# B152X.net
KiCad netlist of a schematic drawn in EAGLE
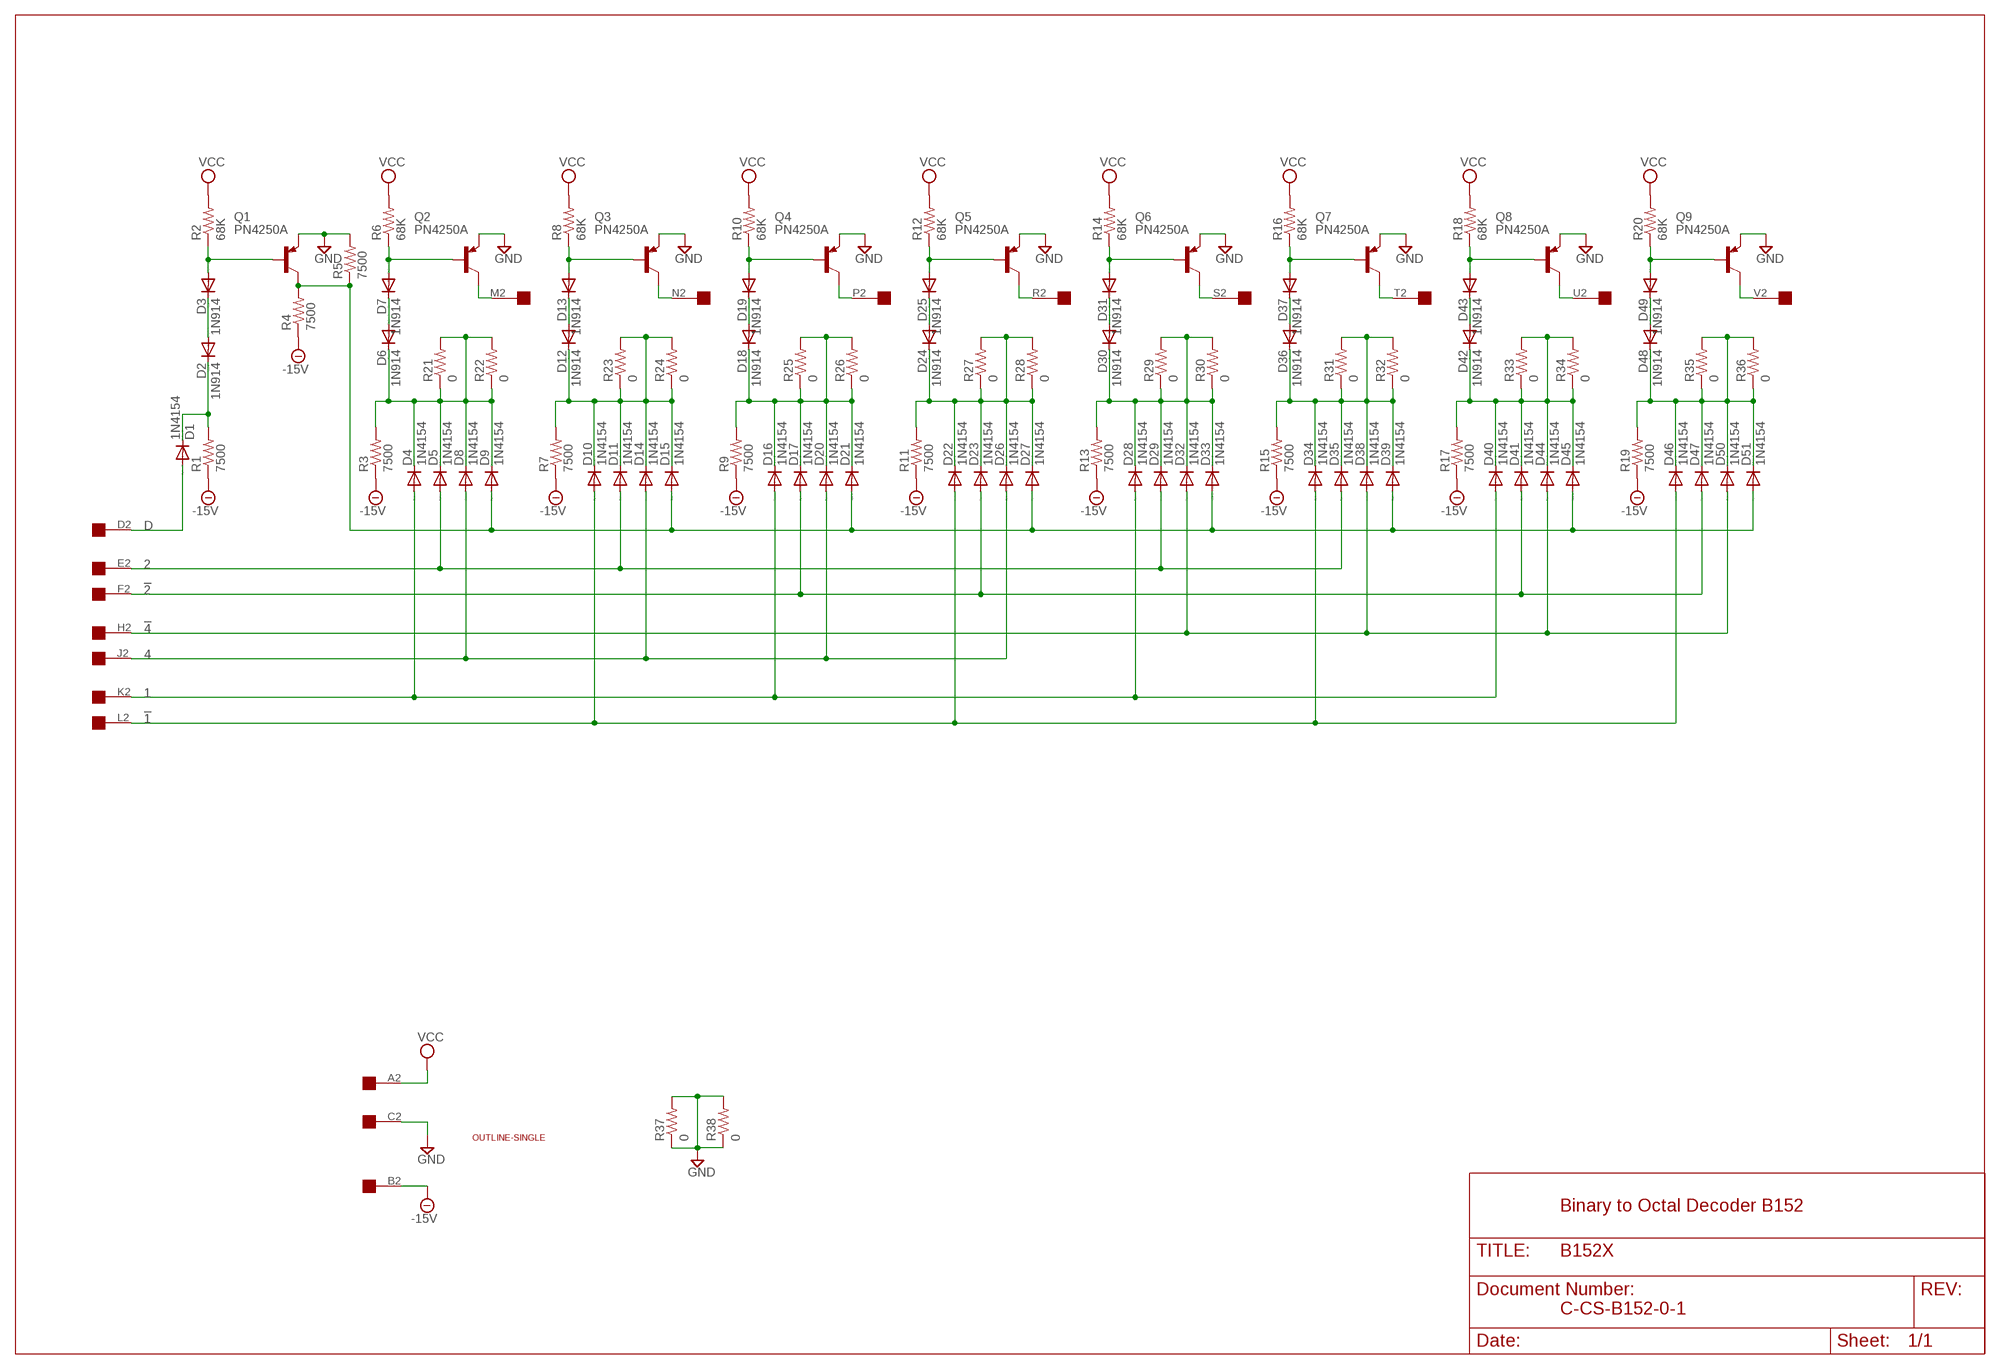
[diagram p0: schematic, sheet 1]

(export (version "E")
  (design (tool "Eeschema 10.0.6"))
  (components
    (comp (ref "D1")
      (value "1N4154")
      (footprint "eagle-import:DO35-10")
      (libsource (lib "eagle-import") (part "DIODE-DO35-10"))
    )
    (comp (ref "D2")
      (value "1N914")
      (footprint "eagle-import:DO35-10")
      (libsource (lib "eagle-import") (part "DIODE-DO35-10"))
    )
    (comp (ref "D3")
      (value "1N914")
      (footprint "eagle-import:DO35-10")
      (libsource (lib "eagle-import") (part "DIODE-DO35-10"))
    )
    (comp (ref "D4")
      (value "1N4154")
      (footprint "eagle-import:DO35-10")
      (libsource (lib "eagle-import") (part "DIODE-DO35-10"))
    )
    (comp (ref "D5")
      (value "1N4154")
      (footprint "eagle-import:DO35-10")
      (libsource (lib "eagle-import") (part "DIODE-DO35-10"))
    )
    (comp (ref "D6")
      (value "1N914")
      (footprint "eagle-import:DO35-10")
      (libsource (lib "eagle-import") (part "DIODE-DO35-10"))
    )
    (comp (ref "D7")
      (value "1N914")
      (footprint "eagle-import:DO35-10")
      (libsource (lib "eagle-import") (part "DIODE-DO35-10"))
    )
    (comp (ref "D8")
      (value "1N4154")
      (footprint "eagle-import:DO35-10")
      (libsource (lib "eagle-import") (part "DIODE-DO35-10"))
    )
    (comp (ref "D9")
      (value "1N4154")
      (footprint "eagle-import:DO35-10")
      (libsource (lib "eagle-import") (part "DIODE-DO35-10"))
    )
    (comp (ref "D10")
      (value "1N4154")
      (footprint "eagle-import:DO35-10")
      (libsource (lib "eagle-import") (part "DIODE-DO35-10"))
    )
    (comp (ref "D11")
      (value "1N4154")
      (footprint "eagle-import:DO35-10")
      (libsource (lib "eagle-import") (part "DIODE-DO35-10"))
    )
    (comp (ref "D12")
      (value "1N914")
      (footprint "eagle-import:DO35-10")
      (libsource (lib "eagle-import") (part "DIODE-DO35-10"))
    )
    (comp (ref "D13")
      (value "1N914")
      (footprint "eagle-import:DO35-10")
      (libsource (lib "eagle-import") (part "DIODE-DO35-10"))
    )
    (comp (ref "D14")
      (value "1N4154")
      (footprint "eagle-import:DO35-10")
      (libsource (lib "eagle-import") (part "DIODE-DO35-10"))
    )
    (comp (ref "D15")
      (value "1N4154")
      (footprint "eagle-import:DO35-10")
      (libsource (lib "eagle-import") (part "DIODE-DO35-10"))
    )
    (comp (ref "D16")
      (value "1N4154")
      (footprint "eagle-import:DO35-10")
      (libsource (lib "eagle-import") (part "DIODE-DO35-10"))
    )
    (comp (ref "D17")
      (value "1N4154")
      (footprint "eagle-import:DO35-10")
      (libsource (lib "eagle-import") (part "DIODE-DO35-10"))
    )
    (comp (ref "D18")
      (value "1N914")
      (footprint "eagle-import:DO35-10")
      (libsource (lib "eagle-import") (part "DIODE-DO35-10"))
    )
    (comp (ref "D19")
      (value "1N914")
      (footprint "eagle-import:DO35-10")
      (libsource (lib "eagle-import") (part "DIODE-DO35-10"))
    )
    (comp (ref "D20")
      (value "1N4154")
      (footprint "eagle-import:DO35-10")
      (libsource (lib "eagle-import") (part "DIODE-DO35-10"))
    )
    (comp (ref "D21")
      (value "1N4154")
      (footprint "eagle-import:DO35-10")
      (libsource (lib "eagle-import") (part "DIODE-DO35-10"))
    )
    (comp (ref "D22")
      (value "1N4154")
      (footprint "eagle-import:DO35-10")
      (libsource (lib "eagle-import") (part "DIODE-DO35-10"))
    )
    (comp (ref "D23")
      (value "1N4154")
      (footprint "eagle-import:DO35-10")
      (libsource (lib "eagle-import") (part "DIODE-DO35-10"))
    )
    (comp (ref "D24")
      (value "1N914")
      (footprint "eagle-import:DO35-10")
      (libsource (lib "eagle-import") (part "DIODE-DO35-10"))
    )
    (comp (ref "D25")
      (value "1N914")
      (footprint "eagle-import:DO35-10")
      (libsource (lib "eagle-import") (part "DIODE-DO35-10"))
    )
    (comp (ref "D26")
      (value "1N4154")
      (footprint "eagle-import:DO35-10")
      (libsource (lib "eagle-import") (part "DIODE-DO35-10"))
    )
    (comp (ref "D27")
      (value "1N4154")
      (footprint "eagle-import:DO35-10")
      (libsource (lib "eagle-import") (part "DIODE-DO35-10"))
    )
    (comp (ref "D28")
      (value "1N4154")
      (footprint "eagle-import:DO35-10")
      (libsource (lib "eagle-import") (part "DIODE-DO35-10"))
    )
    (comp (ref "D29")
      (value "1N4154")
      (footprint "eagle-import:DO35-10")
      (libsource (lib "eagle-import") (part "DIODE-DO35-10"))
    )
    (comp (ref "D30")
      (value "1N914")
      (footprint "eagle-import:DO35-10")
      (libsource (lib "eagle-import") (part "DIODE-DO35-10"))
    )
    (comp (ref "D31")
      (value "1N914")
      (footprint "eagle-import:DO35-10")
      (libsource (lib "eagle-import") (part "DIODE-DO35-10"))
    )
    (comp (ref "D32")
      (value "1N4154")
      (footprint "eagle-import:DO35-10")
      (libsource (lib "eagle-import") (part "DIODE-DO35-10"))
    )
    (comp (ref "D33")
      (value "1N4154")
      (footprint "eagle-import:DO35-10")
      (libsource (lib "eagle-import") (part "DIODE-DO35-10"))
    )
    (comp (ref "D34")
      (value "1N4154")
      (footprint "eagle-import:DO35-10")
      (libsource (lib "eagle-import") (part "DIODE-DO35-10"))
    )
    (comp (ref "D35")
      (value "1N4154")
      (footprint "eagle-import:DO35-10")
      (libsource (lib "eagle-import") (part "DIODE-DO35-10"))
    )
    (comp (ref "D36")
      (value "1N914")
      (footprint "eagle-import:DO35-10")
      (libsource (lib "eagle-import") (part "DIODE-DO35-10"))
    )
    (comp (ref "D37")
      (value "1N914")
      (footprint "eagle-import:DO35-10")
      (libsource (lib "eagle-import") (part "DIODE-DO35-10"))
    )
    (comp (ref "D38")
      (value "1N4154")
      (footprint "eagle-import:DO35-10")
      (libsource (lib "eagle-import") (part "DIODE-DO35-10"))
    )
    (comp (ref "D39")
      (value "1N4154")
      (footprint "eagle-import:DO35-10")
      (libsource (lib "eagle-import") (part "DIODE-DO35-10"))
    )
    (comp (ref "D40")
      (value "1N4154")
      (footprint "eagle-import:DO35-10")
      (libsource (lib "eagle-import") (part "DIODE-DO35-10"))
    )
    (comp (ref "D41")
      (value "1N4154")
      (footprint "eagle-import:DO35-10")
      (libsource (lib "eagle-import") (part "DIODE-DO35-10"))
    )
    (comp (ref "D42")
      (value "1N914")
      (footprint "eagle-import:DO35-10")
      (libsource (lib "eagle-import") (part "DIODE-DO35-10"))
    )
    (comp (ref "D43")
      (value "1N914")
      (footprint "eagle-import:DO35-10")
      (libsource (lib "eagle-import") (part "DIODE-DO35-10"))
    )
    (comp (ref "D44")
      (value "1N4154")
      (footprint "eagle-import:DO35-10")
      (libsource (lib "eagle-import") (part "DIODE-DO35-10"))
    )
    (comp (ref "D45")
      (value "1N4154")
      (footprint "eagle-import:DO35-10")
      (libsource (lib "eagle-import") (part "DIODE-DO35-10"))
    )
    (comp (ref "D46")
      (value "1N4154")
      (footprint "eagle-import:DO35-10")
      (libsource (lib "eagle-import") (part "DIODE-DO35-10"))
    )
    (comp (ref "D47")
      (value "1N4154")
      (footprint "eagle-import:DO35-10")
      (libsource (lib "eagle-import") (part "DIODE-DO35-10"))
    )
    (comp (ref "D48")
      (value "1N914")
      (footprint "eagle-import:DO35-10")
      (libsource (lib "eagle-import") (part "DIODE-DO35-10"))
    )
    (comp (ref "D49")
      (value "1N914")
      (footprint "eagle-import:DO35-10")
      (libsource (lib "eagle-import") (part "DIODE-DO35-10"))
    )
    (comp (ref "D50")
      (value "1N4154")
      (footprint "eagle-import:DO35-10")
      (libsource (lib "eagle-import") (part "DIODE-DO35-10"))
    )
    (comp (ref "D51")
      (value "1N4154")
      (footprint "eagle-import:DO35-10")
      (libsource (lib "eagle-import") (part "DIODE-DO35-10"))
    )
    (comp (ref "Q1")
      (value "PN4250A")
      (footprint "eagle-import:TO5")
      (libsource (lib "eagle-import") (part "-PNP-TO5"))
    )
    (comp (ref "Q2")
      (value "PN4250A")
      (footprint "eagle-import:TO5")
      (libsource (lib "eagle-import") (part "-PNP-TO5"))
    )
    (comp (ref "Q3")
      (value "PN4250A")
      (footprint "eagle-import:TO5")
      (libsource (lib "eagle-import") (part "-PNP-TO5"))
    )
    (comp (ref "Q4")
      (value "PN4250A")
      (footprint "eagle-import:TO5")
      (libsource (lib "eagle-import") (part "-PNP-TO5"))
    )
    (comp (ref "Q5")
      (value "PN4250A")
      (footprint "eagle-import:TO5")
      (libsource (lib "eagle-import") (part "-PNP-TO5"))
    )
    (comp (ref "Q6")
      (value "PN4250A")
      (footprint "eagle-import:TO5")
      (libsource (lib "eagle-import") (part "-PNP-TO5"))
    )
    (comp (ref "Q7")
      (value "PN4250A")
      (footprint "eagle-import:TO5")
      (libsource (lib "eagle-import") (part "-PNP-TO5"))
    )
    (comp (ref "Q8")
      (value "PN4250A")
      (footprint "eagle-import:TO5")
      (libsource (lib "eagle-import") (part "-PNP-TO5"))
    )
    (comp (ref "Q9")
      (value "PN4250A")
      (footprint "eagle-import:TO5")
      (libsource (lib "eagle-import") (part "-PNP-TO5"))
    )
    (comp (ref "R1")
      (value "7500")
      (footprint "eagle-import:0207_10")
      (libsource (lib "eagle-import") (part "R-US_0207/10"))
    )
    (comp (ref "R2")
      (value "68K")
      (footprint "eagle-import:0207_10")
      (libsource (lib "eagle-import") (part "R-US_0207/10"))
    )
    (comp (ref "R3")
      (value "7500")
      (footprint "eagle-import:0207_10")
      (libsource (lib "eagle-import") (part "R-US_0207/10"))
    )
    (comp (ref "R4")
      (value "7500")
      (footprint "eagle-import:0207_10")
      (libsource (lib "eagle-import") (part "R-US_0207/10"))
    )
    (comp (ref "R5")
      (value "7500")
      (footprint "eagle-import:0207_10")
      (libsource (lib "eagle-import") (part "R-US_0207/10"))
    )
    (comp (ref "R6")
      (value "68K")
      (footprint "eagle-import:0207_10")
      (libsource (lib "eagle-import") (part "R-US_0207/10"))
    )
    (comp (ref "R7")
      (value "7500")
      (footprint "eagle-import:0207_10")
      (libsource (lib "eagle-import") (part "R-US_0207/10"))
    )
    (comp (ref "R8")
      (value "68K")
      (footprint "eagle-import:0207_10")
      (libsource (lib "eagle-import") (part "R-US_0207/10"))
    )
    (comp (ref "R9")
      (value "7500")
      (footprint "eagle-import:0207_10")
      (libsource (lib "eagle-import") (part "R-US_0207/10"))
    )
    (comp (ref "R10")
      (value "68K")
      (footprint "eagle-import:0207_10")
      (libsource (lib "eagle-import") (part "R-US_0207/10"))
    )
    (comp (ref "R11")
      (value "7500")
      (footprint "eagle-import:0207_10")
      (libsource (lib "eagle-import") (part "R-US_0207/10"))
    )
    (comp (ref "R12")
      (value "68K")
      (footprint "eagle-import:0207_10")
      (libsource (lib "eagle-import") (part "R-US_0207/10"))
    )
    (comp (ref "R13")
      (value "7500")
      (footprint "eagle-import:0207_10")
      (libsource (lib "eagle-import") (part "R-US_0207/10"))
    )
    (comp (ref "R14")
      (value "68K")
      (footprint "eagle-import:0207_10")
      (libsource (lib "eagle-import") (part "R-US_0207/10"))
    )
    (comp (ref "R15")
      (value "7500")
      (footprint "eagle-import:0207_10")
      (libsource (lib "eagle-import") (part "R-US_0207/10"))
    )
    (comp (ref "R16")
      (value "68K")
      (footprint "eagle-import:0207_10")
      (libsource (lib "eagle-import") (part "R-US_0207/10"))
    )
    (comp (ref "R17")
      (value "7500")
      (footprint "eagle-import:0207_10")
      (libsource (lib "eagle-import") (part "R-US_0207/10"))
    )
    (comp (ref "R18")
      (value "68K")
      (footprint "eagle-import:0207_10")
      (libsource (lib "eagle-import") (part "R-US_0207/10"))
    )
    (comp (ref "R19")
      (value "7500")
      (footprint "eagle-import:0207_10")
      (libsource (lib "eagle-import") (part "R-US_0207/10"))
    )
    (comp (ref "R20")
      (value "68K")
      (footprint "eagle-import:0207_10")
      (libsource (lib "eagle-import") (part "R-US_0207/10"))
    )
    (comp (ref "R21")
      (value "0")
      (footprint "eagle-import:0207_10")
      (libsource (lib "eagle-import") (part "R-US_0207/10"))
    )
    (comp (ref "R22")
      (value "0")
      (footprint "eagle-import:0207_10")
      (libsource (lib "eagle-import") (part "R-US_0207/10"))
    )
    (comp (ref "R23")
      (value "0")
      (footprint "eagle-import:0207_10")
      (libsource (lib "eagle-import") (part "R-US_0207/10"))
    )
    (comp (ref "R24")
      (value "0")
      (footprint "eagle-import:0207_10")
      (libsource (lib "eagle-import") (part "R-US_0207/10"))
    )
    (comp (ref "R25")
      (value "0")
      (footprint "eagle-import:0207_10")
      (libsource (lib "eagle-import") (part "R-US_0207/10"))
    )
    (comp (ref "R26")
      (value "0")
      (footprint "eagle-import:0207_10")
      (libsource (lib "eagle-import") (part "R-US_0207/10"))
    )
    (comp (ref "R27")
      (value "0")
      (footprint "eagle-import:0207_10")
      (libsource (lib "eagle-import") (part "R-US_0207/10"))
    )
    (comp (ref "R28")
      (value "0")
      (footprint "eagle-import:0207_10")
      (libsource (lib "eagle-import") (part "R-US_0207/10"))
    )
    (comp (ref "R29")
      (value "0")
      (footprint "eagle-import:0207_10")
      (libsource (lib "eagle-import") (part "R-US_0207/10"))
    )
    (comp (ref "R30")
      (value "0")
      (footprint "eagle-import:0207_10")
      (libsource (lib "eagle-import") (part "R-US_0207/10"))
    )
    (comp (ref "R31")
      (value "0")
      (footprint "eagle-import:0207_10")
      (libsource (lib "eagle-import") (part "R-US_0207/10"))
    )
    (comp (ref "R32")
      (value "0")
      (footprint "eagle-import:0207_10")
      (libsource (lib "eagle-import") (part "R-US_0207/10"))
    )
    (comp (ref "R33")
      (value "0")
      (footprint "eagle-import:0207_10")
      (libsource (lib "eagle-import") (part "R-US_0207/10"))
    )
    (comp (ref "R34")
      (value "0")
      (footprint "eagle-import:0207_10")
      (libsource (lib "eagle-import") (part "R-US_0207/10"))
    )
    (comp (ref "R35")
      (value "0")
      (footprint "eagle-import:0207_10")
      (libsource (lib "eagle-import") (part "R-US_0207/10"))
    )
    (comp (ref "R36")
      (value "0")
      (footprint "eagle-import:0207_10")
      (libsource (lib "eagle-import") (part "R-US_0207/10"))
    )
    (comp (ref "R37")
      (value "0")
      (footprint "eagle-import:0207_10")
      (libsource (lib "eagle-import") (part "R-US_0207/10"))
    )
    (comp (ref "R38")
      (value "0")
      (footprint "eagle-import:0207_10")
      (libsource (lib "eagle-import") (part "R-US_0207/10"))
    )
    (comp (ref "U$1")
      (value "OUTLINE-SINGLE")
      (footprint "eagle-import:SINGLE")
      (libsource (lib "eagle-import") (part "OUTLINE-SINGLE"))
    )
    (comp (ref "U$2")
      (value "EDGE-1")
      (footprint "eagle-import:EDGE-CON1")
      (libsource (lib "eagle-import") (part "EDGE-1"))
    )
  )
  (nets
    (net (code "1") (name "-15V") (class "Default")
      (node (ref "R1") (pin "1") (pinfunction "1_1") (pintype "passive"))
      (node (ref "R11") (pin "1") (pinfunction "1_1") (pintype "passive"))
      (node (ref "R13") (pin "1") (pinfunction "1_1") (pintype "passive"))
      (node (ref "R15") (pin "1") (pinfunction "1_1") (pintype "passive"))
      (node (ref "R17") (pin "1") (pinfunction "1_1") (pintype "passive"))
      (node (ref "R19") (pin "1") (pinfunction "1_1") (pintype "passive"))
      (node (ref "R3") (pin "1") (pinfunction "1_1") (pintype "passive"))
      (node (ref "R4") (pin "1") (pinfunction "1_1") (pintype "passive"))
      (node (ref "R7") (pin "1") (pinfunction "1_1") (pintype "passive"))
      (node (ref "R9") (pin "1") (pinfunction "1_1") (pintype "passive"))
      (node (ref "U$2") (pin "B2") (pinfunction "1_B2") (pintype "bidirectional"))
    )
    (net (code "2") (name "/1") (class "Default")
      (node (ref "D16") (pin "A") (pinfunction "A_A") (pintype "passive"))
      (node (ref "D28") (pin "A") (pinfunction "A_A") (pintype "passive"))
      (node (ref "D4") (pin "A") (pinfunction "A_A") (pintype "passive"))
      (node (ref "D40") (pin "A") (pinfunction "A_A") (pintype "passive"))
      (node (ref "U$2") (pin "K2") (pinfunction "1_K2") (pintype "bidirectional"))
    )
    (net (code "3") (name "/2") (class "Default")
      (node (ref "D11") (pin "A") (pinfunction "A_A") (pintype "passive"))
      (node (ref "D29") (pin "A") (pinfunction "A_A") (pintype "passive"))
      (node (ref "D35") (pin "A") (pinfunction "A_A") (pintype "passive"))
      (node (ref "D5") (pin "A") (pinfunction "A_A") (pintype "passive"))
      (node (ref "U$2") (pin "E2") (pinfunction "1_E2") (pintype "bidirectional"))
    )
    (net (code "4") (name "/4") (class "Default")
      (node (ref "D14") (pin "A") (pinfunction "A_A") (pintype "passive"))
      (node (ref "D20") (pin "A") (pinfunction "A_A") (pintype "passive"))
      (node (ref "D26") (pin "A") (pinfunction "A_A") (pintype "passive"))
      (node (ref "D8") (pin "A") (pinfunction "A_A") (pintype "passive"))
      (node (ref "U$2") (pin "J2") (pinfunction "1_J2") (pintype "bidirectional"))
    )
    (net (code "5") (name "/D") (class "Default")
      (node (ref "D1") (pin "A") (pinfunction "A_A") (pintype "passive"))
      (node (ref "U$2") (pin "D2") (pinfunction "1_D2") (pintype "bidirectional"))
    )
    (net (code "6") (name "/~{1}") (class "Default")
      (node (ref "D10") (pin "A") (pinfunction "A_A") (pintype "passive"))
      (node (ref "D22") (pin "A") (pinfunction "A_A") (pintype "passive"))
      (node (ref "D34") (pin "A") (pinfunction "A_A") (pintype "passive"))
      (node (ref "D46") (pin "A") (pinfunction "A_A") (pintype "passive"))
      (node (ref "U$2") (pin "L2") (pinfunction "1_L2") (pintype "bidirectional"))
    )
    (net (code "7") (name "/~{2}") (class "Default")
      (node (ref "D17") (pin "A") (pinfunction "A_A") (pintype "passive"))
      (node (ref "D23") (pin "A") (pinfunction "A_A") (pintype "passive"))
      (node (ref "D41") (pin "A") (pinfunction "A_A") (pintype "passive"))
      (node (ref "D47") (pin "A") (pinfunction "A_A") (pintype "passive"))
      (node (ref "U$2") (pin "F2") (pinfunction "1_F2") (pintype "bidirectional"))
    )
    (net (code "8") (name "/~{4}") (class "Default")
      (node (ref "D32") (pin "A") (pinfunction "A_A") (pintype "passive"))
      (node (ref "D38") (pin "A") (pinfunction "A_A") (pintype "passive"))
      (node (ref "D44") (pin "A") (pinfunction "A_A") (pintype "passive"))
      (node (ref "D50") (pin "A") (pinfunction "A_A") (pintype "passive"))
      (node (ref "U$2") (pin "H2") (pinfunction "1_H2") (pintype "bidirectional"))
    )
    (net (code "9") (name "GND") (class "Default")
      (node (ref "Q1") (pin "1") (pinfunction "E_1") (pintype "passive"))
      (node (ref "Q2") (pin "1") (pinfunction "E_1") (pintype "passive"))
      (node (ref "Q3") (pin "1") (pinfunction "E_1") (pintype "passive"))
      (node (ref "Q4") (pin "1") (pinfunction "E_1") (pintype "passive"))
      (node (ref "Q5") (pin "1") (pinfunction "E_1") (pintype "passive"))
      (node (ref "Q6") (pin "1") (pinfunction "E_1") (pintype "passive"))
      (node (ref "Q7") (pin "1") (pinfunction "E_1") (pintype "passive"))
      (node (ref "Q8") (pin "1") (pinfunction "E_1") (pintype "passive"))
      (node (ref "Q9") (pin "1") (pinfunction "E_1") (pintype "passive"))
      (node (ref "R37") (pin "1") (pinfunction "1_1") (pintype "passive"))
      (node (ref "R37") (pin "2") (pinfunction "2_2") (pintype "passive"))
      (node (ref "R38") (pin "1") (pinfunction "1_1") (pintype "passive"))
      (node (ref "R38") (pin "2") (pinfunction "2_2") (pintype "passive"))
      (node (ref "R5") (pin "2") (pinfunction "2_2") (pintype "passive"))
      (node (ref "U$2") (pin "C2") (pinfunction "1_C2") (pintype "bidirectional"))
    )
    (net (code "10") (name "Net-(D1-PadC)") (class "Default")
      (node (ref "D1") (pin "C") (pinfunction "C_C") (pintype "passive"))
      (node (ref "D2") (pin "C") (pinfunction "C_C") (pintype "passive"))
      (node (ref "R1") (pin "2") (pinfunction "2_2") (pintype "passive"))
    )
    (net (code "11") (name "Net-(D2-PadA)") (class "Default")
      (node (ref "D2") (pin "A") (pinfunction "A_A") (pintype "passive"))
      (node (ref "D3") (pin "C") (pinfunction "C_C") (pintype "passive"))
    )
    (net (code "12") (name "Net-(D4-PadC)") (class "Default")
      (node (ref "D4") (pin "C") (pinfunction "C_C") (pintype "passive"))
      (node (ref "D5") (pin "C") (pinfunction "C_C") (pintype "passive"))
      (node (ref "D6") (pin "C") (pinfunction "C_C") (pintype "passive"))
      (node (ref "D8") (pin "C") (pinfunction "C_C") (pintype "passive"))
      (node (ref "D9") (pin "C") (pinfunction "C_C") (pintype "passive"))
      (node (ref "R21") (pin "1") (pinfunction "1_1") (pintype "passive"))
      (node (ref "R21") (pin "2") (pinfunction "2_2") (pintype "passive"))
      (node (ref "R22") (pin "1") (pinfunction "1_1") (pintype "passive"))
      (node (ref "R22") (pin "2") (pinfunction "2_2") (pintype "passive"))
      (node (ref "R3") (pin "2") (pinfunction "2_2") (pintype "passive"))
    )
    (net (code "13") (name "Net-(D6-PadA)") (class "Default")
      (node (ref "D6") (pin "A") (pinfunction "A_A") (pintype "passive"))
      (node (ref "D7") (pin "C") (pinfunction "C_C") (pintype "passive"))
    )
    (net (code "14") (name "Net-(D10-PadC)") (class "Default")
      (node (ref "D10") (pin "C") (pinfunction "C_C") (pintype "passive"))
      (node (ref "D11") (pin "C") (pinfunction "C_C") (pintype "passive"))
      (node (ref "D12") (pin "C") (pinfunction "C_C") (pintype "passive"))
      (node (ref "D14") (pin "C") (pinfunction "C_C") (pintype "passive"))
      (node (ref "D15") (pin "C") (pinfunction "C_C") (pintype "passive"))
      (node (ref "R23") (pin "1") (pinfunction "1_1") (pintype "passive"))
      (node (ref "R23") (pin "2") (pinfunction "2_2") (pintype "passive"))
      (node (ref "R24") (pin "1") (pinfunction "1_1") (pintype "passive"))
      (node (ref "R24") (pin "2") (pinfunction "2_2") (pintype "passive"))
      (node (ref "R7") (pin "2") (pinfunction "2_2") (pintype "passive"))
    )
    (net (code "15") (name "Net-(D12-PadA)") (class "Default")
      (node (ref "D12") (pin "A") (pinfunction "A_A") (pintype "passive"))
      (node (ref "D13") (pin "C") (pinfunction "C_C") (pintype "passive"))
    )
    (net (code "16") (name "Net-(D16-PadC)") (class "Default")
      (node (ref "D16") (pin "C") (pinfunction "C_C") (pintype "passive"))
      (node (ref "D17") (pin "C") (pinfunction "C_C") (pintype "passive"))
      (node (ref "D18") (pin "C") (pinfunction "C_C") (pintype "passive"))
      (node (ref "D20") (pin "C") (pinfunction "C_C") (pintype "passive"))
      (node (ref "D21") (pin "C") (pinfunction "C_C") (pintype "passive"))
      (node (ref "R25") (pin "1") (pinfunction "1_1") (pintype "passive"))
      (node (ref "R25") (pin "2") (pinfunction "2_2") (pintype "passive"))
      (node (ref "R26") (pin "1") (pinfunction "1_1") (pintype "passive"))
      (node (ref "R26") (pin "2") (pinfunction "2_2") (pintype "passive"))
      (node (ref "R9") (pin "2") (pinfunction "2_2") (pintype "passive"))
    )
    (net (code "17") (name "Net-(D18-PadA)") (class "Default")
      (node (ref "D18") (pin "A") (pinfunction "A_A") (pintype "passive"))
      (node (ref "D19") (pin "C") (pinfunction "C_C") (pintype "passive"))
    )
    (net (code "18") (name "Net-(D22-PadC)") (class "Default")
      (node (ref "D22") (pin "C") (pinfunction "C_C") (pintype "passive"))
      (node (ref "D23") (pin "C") (pinfunction "C_C") (pintype "passive"))
      (node (ref "D24") (pin "C") (pinfunction "C_C") (pintype "passive"))
      (node (ref "D26") (pin "C") (pinfunction "C_C") (pintype "passive"))
      (node (ref "D27") (pin "C") (pinfunction "C_C") (pintype "passive"))
      (node (ref "R11") (pin "2") (pinfunction "2_2") (pintype "passive"))
      (node (ref "R27") (pin "1") (pinfunction "1_1") (pintype "passive"))
      (node (ref "R27") (pin "2") (pinfunction "2_2") (pintype "passive"))
      (node (ref "R28") (pin "1") (pinfunction "1_1") (pintype "passive"))
      (node (ref "R28") (pin "2") (pinfunction "2_2") (pintype "passive"))
    )
    (net (code "19") (name "Net-(D24-PadA)") (class "Default")
      (node (ref "D24") (pin "A") (pinfunction "A_A") (pintype "passive"))
      (node (ref "D25") (pin "C") (pinfunction "C_C") (pintype "passive"))
    )
    (net (code "20") (name "Net-(D28-PadC)") (class "Default")
      (node (ref "D28") (pin "C") (pinfunction "C_C") (pintype "passive"))
      (node (ref "D29") (pin "C") (pinfunction "C_C") (pintype "passive"))
      (node (ref "D30") (pin "C") (pinfunction "C_C") (pintype "passive"))
      (node (ref "D32") (pin "C") (pinfunction "C_C") (pintype "passive"))
      (node (ref "D33") (pin "C") (pinfunction "C_C") (pintype "passive"))
      (node (ref "R13") (pin "2") (pinfunction "2_2") (pintype "passive"))
      (node (ref "R29") (pin "1") (pinfunction "1_1") (pintype "passive"))
      (node (ref "R29") (pin "2") (pinfunction "2_2") (pintype "passive"))
      (node (ref "R30") (pin "1") (pinfunction "1_1") (pintype "passive"))
      (node (ref "R30") (pin "2") (pinfunction "2_2") (pintype "passive"))
    )
    (net (code "21") (name "Net-(D30-PadA)") (class "Default")
      (node (ref "D30") (pin "A") (pinfunction "A_A") (pintype "passive"))
      (node (ref "D31") (pin "C") (pinfunction "C_C") (pintype "passive"))
    )
    (net (code "22") (name "Net-(D34-PadC)") (class "Default")
      (node (ref "D34") (pin "C") (pinfunction "C_C") (pintype "passive"))
      (node (ref "D35") (pin "C") (pinfunction "C_C") (pintype "passive"))
      (node (ref "D36") (pin "C") (pinfunction "C_C") (pintype "passive"))
      (node (ref "D38") (pin "C") (pinfunction "C_C") (pintype "passive"))
      (node (ref "D39") (pin "C") (pinfunction "C_C") (pintype "passive"))
      (node (ref "R15") (pin "2") (pinfunction "2_2") (pintype "passive"))
      (node (ref "R31") (pin "1") (pinfunction "1_1") (pintype "passive"))
      (node (ref "R31") (pin "2") (pinfunction "2_2") (pintype "passive"))
      (node (ref "R32") (pin "1") (pinfunction "1_1") (pintype "passive"))
      (node (ref "R32") (pin "2") (pinfunction "2_2") (pintype "passive"))
    )
    (net (code "23") (name "Net-(D36-PadA)") (class "Default")
      (node (ref "D36") (pin "A") (pinfunction "A_A") (pintype "passive"))
      (node (ref "D37") (pin "C") (pinfunction "C_C") (pintype "passive"))
    )
    (net (code "24") (name "Net-(D40-PadC)") (class "Default")
      (node (ref "D40") (pin "C") (pinfunction "C_C") (pintype "passive"))
      (node (ref "D41") (pin "C") (pinfunction "C_C") (pintype "passive"))
      (node (ref "D42") (pin "C") (pinfunction "C_C") (pintype "passive"))
      (node (ref "D44") (pin "C") (pinfunction "C_C") (pintype "passive"))
      (node (ref "D45") (pin "C") (pinfunction "C_C") (pintype "passive"))
      (node (ref "R17") (pin "2") (pinfunction "2_2") (pintype "passive"))
      (node (ref "R33") (pin "1") (pinfunction "1_1") (pintype "passive"))
      (node (ref "R33") (pin "2") (pinfunction "2_2") (pintype "passive"))
      (node (ref "R34") (pin "1") (pinfunction "1_1") (pintype "passive"))
      (node (ref "R34") (pin "2") (pinfunction "2_2") (pintype "passive"))
    )
    (net (code "25") (name "Net-(D42-PadA)") (class "Default")
      (node (ref "D42") (pin "A") (pinfunction "A_A") (pintype "passive"))
      (node (ref "D43") (pin "C") (pinfunction "C_C") (pintype "passive"))
    )
    (net (code "26") (name "Net-(D46-PadC)") (class "Default")
      (node (ref "D46") (pin "C") (pinfunction "C_C") (pintype "passive"))
      (node (ref "D47") (pin "C") (pinfunction "C_C") (pintype "passive"))
      (node (ref "D48") (pin "C") (pinfunction "C_C") (pintype "passive"))
      (node (ref "D50") (pin "C") (pinfunction "C_C") (pintype "passive"))
      (node (ref "D51") (pin "C") (pinfunction "C_C") (pintype "passive"))
      (node (ref "R19") (pin "2") (pinfunction "2_2") (pintype "passive"))
      (node (ref "R35") (pin "1") (pinfunction "1_1") (pintype "passive"))
      (node (ref "R35") (pin "2") (pinfunction "2_2") (pintype "passive"))
      (node (ref "R36") (pin "1") (pinfunction "1_1") (pintype "passive"))
      (node (ref "R36") (pin "2") (pinfunction "2_2") (pintype "passive"))
    )
    (net (code "27") (name "Net-(D48-PadA)") (class "Default")
      (node (ref "D48") (pin "A") (pinfunction "A_A") (pintype "passive"))
      (node (ref "D49") (pin "C") (pinfunction "C_C") (pintype "passive"))
    )
    (net (code "28") (name "Net-(Q1-B)") (class "Default")
      (node (ref "D3") (pin "A") (pinfunction "A_A") (pintype "passive"))
      (node (ref "Q1") (pin "2") (pinfunction "B_2") (pintype "passive"))
      (node (ref "R2") (pin "1") (pinfunction "1_1") (pintype "passive"))
    )
    (net (code "29") (name "Net-(Q1-C)") (class "Default")
      (node (ref "D15") (pin "A") (pinfunction "A_A") (pintype "passive"))
      (node (ref "D21") (pin "A") (pinfunction "A_A") (pintype "passive"))
      (node (ref "D27") (pin "A") (pinfunction "A_A") (pintype "passive"))
      (node (ref "D33") (pin "A") (pinfunction "A_A") (pintype "passive"))
      (node (ref "D39") (pin "A") (pinfunction "A_A") (pintype "passive"))
      (node (ref "D45") (pin "A") (pinfunction "A_A") (pintype "passive"))
      (node (ref "D51") (pin "A") (pinfunction "A_A") (pintype "passive"))
      (node (ref "D9") (pin "A") (pinfunction "A_A") (pintype "passive"))
      (node (ref "Q1") (pin "3") (pinfunction "C_3") (pintype "passive"))
      (node (ref "R4") (pin "2") (pinfunction "2_2") (pintype "passive"))
      (node (ref "R5") (pin "1") (pinfunction "1_1") (pintype "passive"))
    )
    (net (code "30") (name "Net-(Q2-B)") (class "Default")
      (node (ref "D7") (pin "A") (pinfunction "A_A") (pintype "passive"))
      (node (ref "Q2") (pin "2") (pinfunction "B_2") (pintype "passive"))
      (node (ref "R6") (pin "1") (pinfunction "1_1") (pintype "passive"))
    )
    (net (code "31") (name "Net-(Q2-C)") (class "Default")
      (node (ref "Q2") (pin "3") (pinfunction "C_3") (pintype "passive"))
      (node (ref "U$2") (pin "M2") (pinfunction "1_M2") (pintype "bidirectional"))
    )
    (net (code "32") (name "Net-(Q3-B)") (class "Default")
      (node (ref "D13") (pin "A") (pinfunction "A_A") (pintype "passive"))
      (node (ref "Q3") (pin "2") (pinfunction "B_2") (pintype "passive"))
      (node (ref "R8") (pin "1") (pinfunction "1_1") (pintype "passive"))
    )
    (net (code "33") (name "Net-(Q3-C)") (class "Default")
      (node (ref "Q3") (pin "3") (pinfunction "C_3") (pintype "passive"))
      (node (ref "U$2") (pin "N2") (pinfunction "1_N2") (pintype "bidirectional"))
    )
    (net (code "34") (name "Net-(Q4-B)") (class "Default")
      (node (ref "D19") (pin "A") (pinfunction "A_A") (pintype "passive"))
      (node (ref "Q4") (pin "2") (pinfunction "B_2") (pintype "passive"))
      (node (ref "R10") (pin "1") (pinfunction "1_1") (pintype "passive"))
    )
    (net (code "35") (name "Net-(Q4-C)") (class "Default")
      (node (ref "Q4") (pin "3") (pinfunction "C_3") (pintype "passive"))
      (node (ref "U$2") (pin "P2") (pinfunction "1_P2") (pintype "bidirectional"))
    )
    (net (code "36") (name "Net-(Q5-B)") (class "Default")
      (node (ref "D25") (pin "A") (pinfunction "A_A") (pintype "passive"))
      (node (ref "Q5") (pin "2") (pinfunction "B_2") (pintype "passive"))
      (node (ref "R12") (pin "1") (pinfunction "1_1") (pintype "passive"))
    )
    (net (code "37") (name "Net-(Q5-C)") (class "Default")
      (node (ref "Q5") (pin "3") (pinfunction "C_3") (pintype "passive"))
      (node (ref "U$2") (pin "R2") (pinfunction "1_R2") (pintype "bidirectional"))
    )
    (net (code "38") (name "Net-(Q6-B)") (class "Default")
      (node (ref "D31") (pin "A") (pinfunction "A_A") (pintype "passive"))
      (node (ref "Q6") (pin "2") (pinfunction "B_2") (pintype "passive"))
      (node (ref "R14") (pin "1") (pinfunction "1_1") (pintype "passive"))
    )
    (net (code "39") (name "Net-(Q6-C)") (class "Default")
      (node (ref "Q6") (pin "3") (pinfunction "C_3") (pintype "passive"))
      (node (ref "U$2") (pin "S2") (pinfunction "1_S2") (pintype "bidirectional"))
    )
    (net (code "40") (name "Net-(Q7-B)") (class "Default")
      (node (ref "D37") (pin "A") (pinfunction "A_A") (pintype "passive"))
      (node (ref "Q7") (pin "2") (pinfunction "B_2") (pintype "passive"))
      (node (ref "R16") (pin "1") (pinfunction "1_1") (pintype "passive"))
    )
    (net (code "41") (name "Net-(Q7-C)") (class "Default")
      (node (ref "Q7") (pin "3") (pinfunction "C_3") (pintype "passive"))
      (node (ref "U$2") (pin "T2") (pinfunction "1_T2") (pintype "bidirectional"))
    )
    (net (code "42") (name "Net-(Q8-B)") (class "Default")
      (node (ref "D43") (pin "A") (pinfunction "A_A") (pintype "passive"))
      (node (ref "Q8") (pin "2") (pinfunction "B_2") (pintype "passive"))
      (node (ref "R18") (pin "1") (pinfunction "1_1") (pintype "passive"))
    )
    (net (code "43") (name "Net-(Q8-C)") (class "Default")
      (node (ref "Q8") (pin "3") (pinfunction "C_3") (pintype "passive"))
      (node (ref "U$2") (pin "U2") (pinfunction "1_U2") (pintype "bidirectional"))
    )
    (net (code "44") (name "Net-(Q9-B)") (class "Default")
      (node (ref "D49") (pin "A") (pinfunction "A_A") (pintype "passive"))
      (node (ref "Q9") (pin "2") (pinfunction "B_2") (pintype "passive"))
      (node (ref "R20") (pin "1") (pinfunction "1_1") (pintype "passive"))
    )
    (net (code "45") (name "Net-(Q9-C)") (class "Default")
      (node (ref "Q9") (pin "3") (pinfunction "C_3") (pintype "passive"))
      (node (ref "U$2") (pin "V2") (pinfunction "1_V2") (pintype "bidirectional"))
    )
    (net (code "46") (name "VCC") (class "Default")
      (node (ref "R10") (pin "2") (pinfunction "2_2") (pintype "passive"))
      (node (ref "R12") (pin "2") (pinfunction "2_2") (pintype "passive"))
      (node (ref "R14") (pin "2") (pinfunction "2_2") (pintype "passive"))
      (node (ref "R16") (pin "2") (pinfunction "2_2") (pintype "passive"))
      (node (ref "R18") (pin "2") (pinfunction "2_2") (pintype "passive"))
      (node (ref "R2") (pin "2") (pinfunction "2_2") (pintype "passive"))
      (node (ref "R20") (pin "2") (pinfunction "2_2") (pintype "passive"))
      (node (ref "R6") (pin "2") (pinfunction "2_2") (pintype "passive"))
      (node (ref "R8") (pin "2") (pinfunction "2_2") (pintype "passive"))
      (node (ref "U$2") (pin "A2") (pinfunction "1_A2") (pintype "bidirectional"))
    )
  )
)
